# Pins.net
KiCad netlist of a schematic drawn in Altium Designer
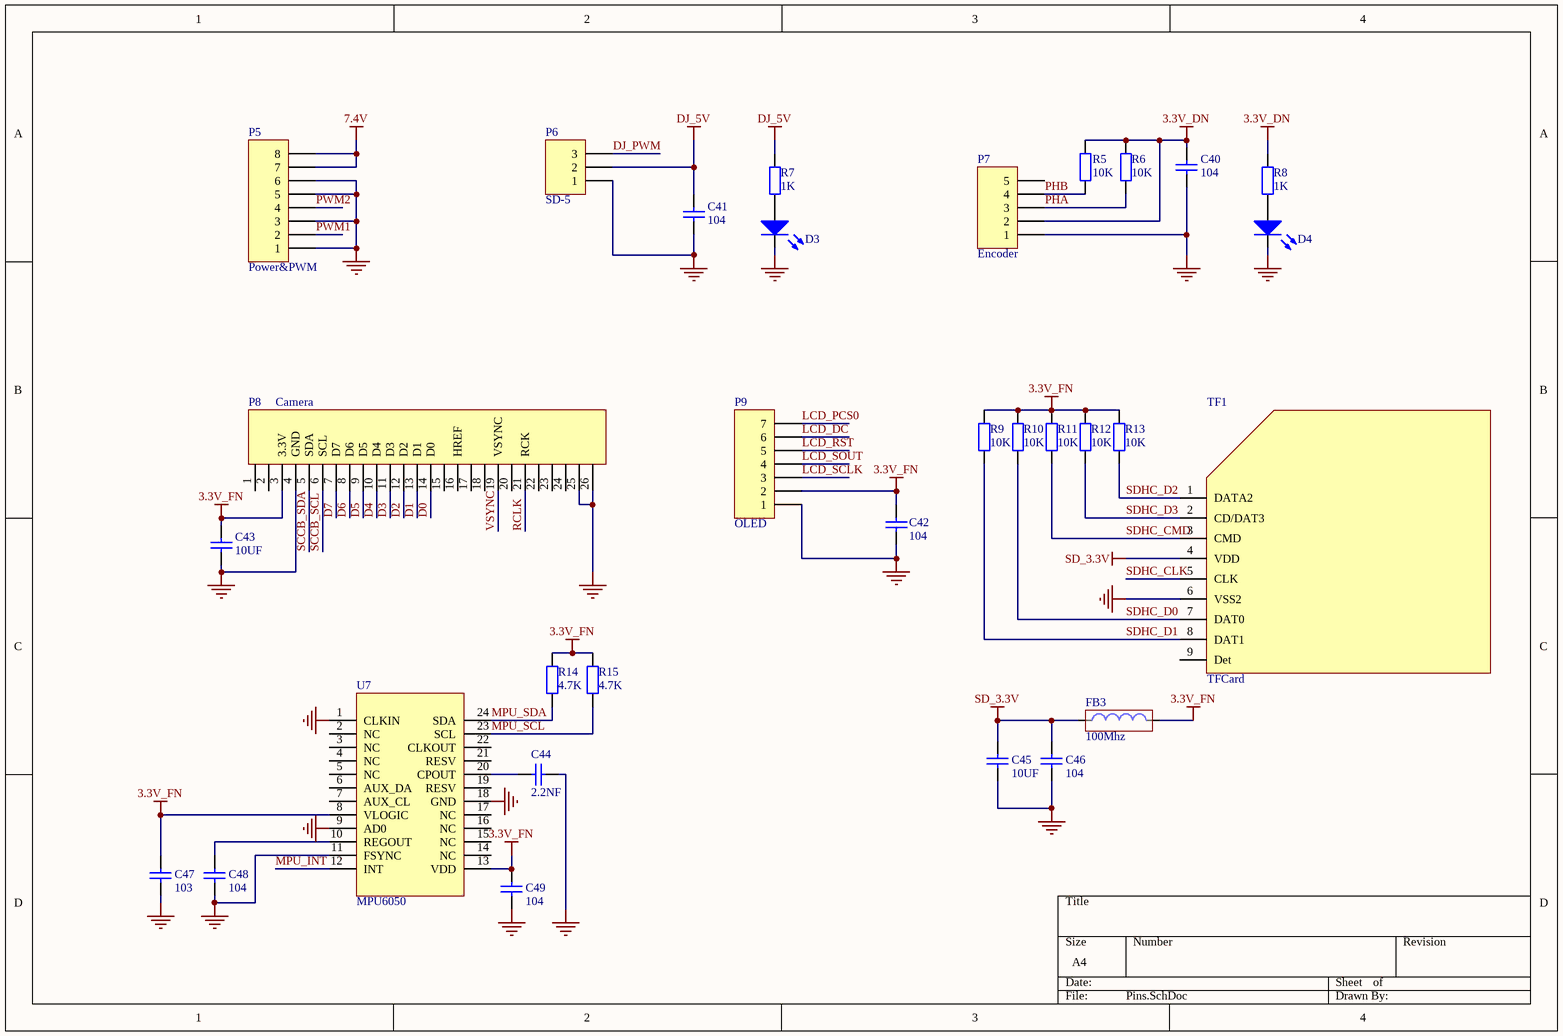
[diagram p0: Pins.SchDoc]

(export (version "E")
  (design (tool "Eeschema 10.0.6"))
  (components
    (comp (ref "C40") (value "104") (footprint "0805") (libsource (lib "飞思卡尔") (part "Cap")))
    (comp (ref "C41") (value "104") (footprint "0805") (libsource (lib "飞思卡尔") (part "Cap")))
    (comp (ref "C42") (value "104") (footprint "0805") (libsource (lib "飞思卡尔") (part "Cap")))
    (comp (ref "C43") (value "10UF") (footprint "1206") (libsource (lib "飞思卡尔") (part "Cap")))
    (comp (ref "C44") (value "2.2NF") (footprint "0805") (libsource (lib "飞思卡尔") (part "Cap")))
    (comp (ref "C45") (value "10UF") (footprint "1206") (libsource (lib "飞思卡尔") (part "Cap")))
    (comp (ref "C46") (value "104") (footprint "0805") (libsource (lib "飞思卡尔") (part "Cap")))
    (comp (ref "C47") (value "103") (footprint "0805") (libsource (lib "飞思卡尔") (part "Cap")))
    (comp (ref "C48") (value "104") (footprint "0805") (libsource (lib "飞思卡尔") (part "Cap")))
    (comp (ref "C49") (value "104") (footprint "0805") (libsource (lib "飞思卡尔") (part "Cap")))
    (comp (ref "D3") (value "Led") (footprint "0805") (libsource (lib "飞思卡尔") (part "Led")))
    (comp (ref "D4") (value "Led") (footprint "0805") (libsource (lib "飞思卡尔") (part "Led")))
    (comp (ref "FB3") (value "100Mhz") (footprint "0805") (libsource (lib "飞思卡尔") (part "Inductor")))
    (comp (ref "P5")
      (value "Power&PWM")
      (footprint "8P-2.54")
      (description "Header, 8-Pin")
      (fields (field (name "PUBLISHER") "Altium Limited"))
      (libsource (lib "Miscellaneous Connectors") (part "Header 8"))
    )
    (comp (ref "P6")
      (value "SD-5")
      (footprint "3PIN-2.54mm")
      (description "Header, 3-Pin")
      (fields (field (name "PUBLISHER") "Altium Limited"))
      (libsource (lib "Miscellaneous Connectors") (part "Header 3"))
    )
    (comp (ref "P7")
      (value "Encoder")
      (footprint "5P-2.54")
      (description "Header, 5-Pin")
      (fields (field (name "PUBLISHER") "Altium Limited"))
      (libsource (lib "Miscellaneous Connectors") (part "Header 5"))
    )
    (comp (ref "P8") (value "Camera") (footprint "FPC-0.5-24P") (libsource (lib "飞思卡尔") (part "野火鹰眼 排线")))
    (comp (ref "P9")
      (value "OLED")
      (footprint "HDR1X7")
      (description "Header, 7-Pin")
      (fields (field (name "PUBLISHER") "Altium Limited"))
      (libsource (lib "Miscellaneous Connectors") (part "Header 7"))
    )
    (comp (ref "R5") (value "10K") (footprint "0805") (libsource (lib "飞思卡尔") (part "Rest")))
    (comp (ref "R6") (value "10K") (footprint "0805") (libsource (lib "飞思卡尔") (part "Rest")))
    (comp (ref "R7") (value "1K") (footprint "0805") (libsource (lib "") (part "Rest_1")))
    (comp (ref "R8") (value "1K") (footprint "0805") (libsource (lib "") (part "Rest_1")))
    (comp (ref "R9") (value "10K") (footprint "0805") (libsource (lib "飞思卡尔") (part "Rest")))
    (comp (ref "R10") (value "10K") (footprint "0805") (libsource (lib "飞思卡尔") (part "Rest")))
    (comp (ref "R11") (value "10K") (footprint "0805") (libsource (lib "飞思卡尔") (part "Rest")))
    (comp (ref "R12") (value "10K") (footprint "0805") (libsource (lib "飞思卡尔") (part "Rest")))
    (comp (ref "R13") (value "10K") (footprint "0805") (libsource (lib "飞思卡尔") (part "Rest")))
    (comp (ref "R14") (value "4.7K") (footprint "0805") (libsource (lib "飞思卡尔") (part "Rest")))
    (comp (ref "R15") (value "4.7K") (footprint "0805") (libsource (lib "飞思卡尔") (part "Rest")))
    (comp (ref "TF1") (value "TFCard") (footprint "SD") (libsource (lib "飞思卡尔") (part "SD卡")))
    (comp (ref "U7") (value "MPU6050") (footprint "QFN-24P") (libsource (lib "飞思卡尔") (part "MPU6050")))
  )
  (nets
    (net (code "1") (name "/D0") (class "Default")
      (node (ref "P8") (pin "14") (pinfunction "D0_14") (pintype "passive"))
    )
    (net (code "2") (name "/D1") (class "Default")
      (node (ref "P8") (pin "13") (pinfunction "D1_13") (pintype "passive"))
    )
    (net (code "3") (name "/D2") (class "Default")
      (node (ref "P8") (pin "12") (pinfunction "D2_12") (pintype "passive"))
    )
    (net (code "4") (name "/D3") (class "Default")
      (node (ref "P8") (pin "11") (pinfunction "D3_11") (pintype "passive"))
    )
    (net (code "5") (name "/D4") (class "Default")
      (node (ref "P8") (pin "10") (pinfunction "D4_10") (pintype "passive"))
    )
    (net (code "6") (name "/D5") (class "Default")
      (node (ref "P8") (pin "9") (pinfunction "D5_9") (pintype "passive"))
    )
    (net (code "7") (name "/D6") (class "Default")
      (node (ref "P8") (pin "8") (pinfunction "D6_8") (pintype "passive"))
    )
    (net (code "8") (name "/D7") (class "Default")
      (node (ref "P8") (pin "7") (pinfunction "D7_7") (pintype "passive"))
    )
    (net (code "9") (name "/DJ_PWM") (class "Default")
      (node (ref "P6") (pin "3") (pinfunction "3_3") (pintype "passive"))
    )
    (net (code "10") (name "/LCD_DC") (class "Default")
      (node (ref "P9") (pin "6") (pinfunction "6_6") (pintype "passive"))
    )
    (net (code "11") (name "/LCD_PCS0") (class "Default")
      (node (ref "P9") (pin "7") (pinfunction "7_7") (pintype "passive"))
    )
    (net (code "12") (name "/LCD_RST") (class "Default")
      (node (ref "P9") (pin "5") (pinfunction "5_5") (pintype "passive"))
    )
    (net (code "13") (name "/LCD_SCLK") (class "Default")
      (node (ref "P9") (pin "3") (pinfunction "3_3") (pintype "passive"))
    )
    (net (code "14") (name "/LCD_SOUT") (class "Default")
      (node (ref "P9") (pin "4") (pinfunction "4_4") (pintype "passive"))
    )
    (net (code "15") (name "/MPU_INT") (class "Default")
      (node (ref "U7") (pin "12") (pinfunction "INT_12") (pintype "passive"))
    )
    (net (code "16") (name "/MPU_SCL") (class "Default")
      (node (ref "R15") (pin "1") (pinfunction "1_1") (pintype "passive"))
      (node (ref "U7") (pin "23") (pinfunction "SCL_23") (pintype "passive"))
    )
    (net (code "17") (name "/MPU_SDA") (class "Default")
      (node (ref "R14") (pin "1") (pinfunction "1_1") (pintype "passive"))
      (node (ref "U7") (pin "24") (pinfunction "SDA_24") (pintype "passive"))
    )
    (net (code "18") (name "/PHA") (class "Default")
      (node (ref "P7") (pin "3") (pinfunction "3_3") (pintype "passive"))
      (node (ref "R6") (pin "1") (pinfunction "1_1") (pintype "passive"))
    )
    (net (code "19") (name "/PHB") (class "Default")
      (node (ref "P7") (pin "4") (pinfunction "4_4") (pintype "passive"))
      (node (ref "R5") (pin "1") (pinfunction "1_1") (pintype "passive"))
    )
    (net (code "20") (name "/PWM1") (class "Default")
      (node (ref "P5") (pin "2") (pinfunction "2_2") (pintype "passive"))
    )
    (net (code "21") (name "/PWM2") (class "Default")
      (node (ref "P5") (pin "4") (pinfunction "4_4") (pintype "passive"))
    )
    (net (code "22") (name "/RCLK") (class "Default")
      (node (ref "P8") (pin "21") (pinfunction "RCK_21") (pintype "passive"))
    )
    (net (code "23") (name "/SCCB_SCL") (class "Default")
      (node (ref "P8") (pin "6") (pinfunction "SCL_6") (pintype "passive"))
    )
    (net (code "24") (name "/SCCB_SDA") (class "Default")
      (node (ref "P8") (pin "5") (pinfunction "SDA_5") (pintype "passive"))
    )
    (net (code "25") (name "/SDHC_CLK") (class "Default")
      (node (ref "TF1") (pin "5") (pinfunction "CLK_5") (pintype "passive"))
    )
    (net (code "26") (name "/SDHC_CMD") (class "Default")
      (node (ref "R11") (pin "1") (pinfunction "1_1") (pintype "passive"))
      (node (ref "TF1") (pin "3") (pinfunction "CMD_3") (pintype "passive"))
    )
    (net (code "27") (name "/SDHC_D0") (class "Default")
      (node (ref "R10") (pin "1") (pinfunction "1_1") (pintype "passive"))
      (node (ref "TF1") (pin "7") (pinfunction "DAT0_7") (pintype "passive"))
    )
    (net (code "28") (name "/SDHC_D1") (class "Default")
      (node (ref "R9") (pin "1") (pinfunction "1_1") (pintype "passive"))
      (node (ref "TF1") (pin "8") (pinfunction "DAT1_8") (pintype "passive"))
    )
    (net (code "29") (name "/SDHC_D2") (class "Default")
      (node (ref "R13") (pin "1") (pinfunction "1_1") (pintype "passive"))
      (node (ref "TF1") (pin "1") (pinfunction "DATA2_1") (pintype "passive"))
    )
    (net (code "30") (name "/SDHC_D3") (class "Default")
      (node (ref "R12") (pin "1") (pinfunction "1_1") (pintype "passive"))
      (node (ref "TF1") (pin "2") (pinfunction "CD/DAT3_2") (pintype "passive"))
    )
    (net (code "31") (name "/VSYNC") (class "Default")
      (node (ref "P8") (pin "19") (pinfunction "VSYNC_19") (pintype "passive"))
    )
    (net (code "32") (name "3.3V_DN") (class "Default")
      (node (ref "C40") (pin "2") (pinfunction "2_2") (pintype "passive"))
      (node (ref "P7") (pin "2") (pinfunction "2_2") (pintype "passive"))
      (node (ref "R5") (pin "2") (pinfunction "2_2") (pintype "passive"))
      (node (ref "R6") (pin "2") (pinfunction "2_2") (pintype "passive"))
      (node (ref "R8") (pin "1") (pinfunction "1_1") (pintype "passive"))
    )
    (net (code "33") (name "3.3V_FN") (class "Default")
      (node (ref "C42") (pin "1") (pinfunction "1_1") (pintype "passive"))
      (node (ref "C43") (pin "2") (pinfunction "2_2") (pintype "passive"))
      (node (ref "C47") (pin "1") (pinfunction "1_1") (pintype "passive"))
      (node (ref "C49") (pin "2") (pinfunction "2_2") (pintype "passive"))
      (node (ref "FB3") (pin "2") (pinfunction "2_2") (pintype "passive"))
      (node (ref "P8") (pin "3") (pinfunction "3.3V_3") (pintype "passive"))
      (node (ref "P9") (pin "2") (pinfunction "2_2") (pintype "passive"))
      (node (ref "R10") (pin "2") (pinfunction "2_2") (pintype "passive"))
      (node (ref "R11") (pin "2") (pinfunction "2_2") (pintype "passive"))
      (node (ref "R12") (pin "2") (pinfunction "2_2") (pintype "passive"))
      (node (ref "R13") (pin "2") (pinfunction "2_2") (pintype "passive"))
      (node (ref "R14") (pin "2") (pinfunction "2_2") (pintype "passive"))
      (node (ref "R15") (pin "2") (pinfunction "2_2") (pintype "passive"))
      (node (ref "R9") (pin "2") (pinfunction "2_2") (pintype "passive"))
      (node (ref "U7") (pin "13") (pinfunction "VDD_13") (pintype "passive"))
      (node (ref "U7") (pin "8") (pinfunction "VLOGIC_8") (pintype "passive"))
    )
    (net (code "34") (name "7.4V") (class "Default")
      (node (ref "P5") (pin "7") (pinfunction "7_7") (pintype "passive"))
      (node (ref "P5") (pin "8") (pinfunction "8_8") (pintype "passive"))
    )
    (net (code "35") (name "DJ_5V") (class "Default")
      (node (ref "C41") (pin "2") (pinfunction "2_2") (pintype "passive"))
      (node (ref "P6") (pin "2") (pinfunction "2_2") (pintype "passive"))
      (node (ref "R7") (pin "1") (pinfunction "1_1") (pintype "passive"))
    )
    (net (code "36") (name "GND") (class "Default")
      (node (ref "C40") (pin "1") (pinfunction "1_1") (pintype "passive"))
      (node (ref "C41") (pin "1") (pinfunction "1_1") (pintype "passive"))
      (node (ref "C42") (pin "2") (pinfunction "2_2") (pintype "passive"))
      (node (ref "C43") (pin "1") (pinfunction "1_1") (pintype "passive"))
      (node (ref "C44") (pin "2") (pinfunction "2_2") (pintype "passive"))
      (node (ref "C45") (pin "2") (pinfunction "2_2") (pintype "passive"))
      (node (ref "C46") (pin "1") (pinfunction "1_1") (pintype "passive"))
      (node (ref "C47") (pin "2") (pinfunction "2_2") (pintype "passive"))
      (node (ref "C48") (pin "1") (pinfunction "1_1") (pintype "passive"))
      (node (ref "C49") (pin "1") (pinfunction "1_1") (pintype "passive"))
      (node (ref "D3") (pin "2") (pinfunction "2_2") (pintype "passive"))
      (node (ref "D4") (pin "2") (pinfunction "2_2") (pintype "passive"))
      (node (ref "P5") (pin "1") (pinfunction "1_1") (pintype "passive"))
      (node (ref "P5") (pin "3") (pinfunction "3_3") (pintype "passive"))
      (node (ref "P5") (pin "5") (pinfunction "5_5") (pintype "passive"))
      (node (ref "P5") (pin "6") (pinfunction "6_6") (pintype "passive"))
      (node (ref "P6") (pin "1") (pinfunction "1_1") (pintype "passive"))
      (node (ref "P7") (pin "1") (pinfunction "1_1") (pintype "passive"))
      (node (ref "P8") (pin "25") (pinfunction "GND_25") (pintype "passive"))
      (node (ref "P8") (pin "26") (pinfunction "GND_26") (pintype "passive"))
      (node (ref "P8") (pin "4") (pinfunction "GND_4") (pintype "passive"))
      (node (ref "P9") (pin "1") (pinfunction "1_1") (pintype "passive"))
      (node (ref "TF1") (pin "6") (pinfunction "VSS2_6") (pintype "passive"))
      (node (ref "U7") (pin "1") (pinfunction "CLKIN_1") (pintype "passive"))
      (node (ref "U7") (pin "11") (pinfunction "FSYNC_11") (pintype "passive"))
      (node (ref "U7") (pin "18") (pinfunction "GND_18") (pintype "passive"))
      (node (ref "U7") (pin "9") (pinfunction "AD0_9") (pintype "passive"))
    )
    (net (code "37") (name "Net-(D3-Pad1)") (class "Default")
      (node (ref "D3") (pin "1") (pinfunction "1_1") (pintype "passive"))
      (node (ref "R7") (pin "2") (pinfunction "2_2") (pintype "passive"))
    )
    (net (code "38") (name "Net-(D4-Pad1)") (class "Default")
      (node (ref "D4") (pin "1") (pinfunction "1_1") (pintype "passive"))
      (node (ref "R8") (pin "2") (pinfunction "2_2") (pintype "passive"))
    )
    (net (code "39") (name "Net-(U7-CPOUT)") (class "Default")
      (node (ref "C44") (pin "1") (pinfunction "1_1") (pintype "passive"))
      (node (ref "U7") (pin "20") (pinfunction "CPOUT_20") (pintype "passive"))
    )
    (net (code "40") (name "Net-(U7-REGOUT)") (class "Default")
      (node (ref "C48") (pin "2") (pinfunction "2_2") (pintype "passive"))
      (node (ref "U7") (pin "10") (pinfunction "REGOUT_10") (pintype "passive"))
    )
    (net (code "41") (name "SD_3.3V") (class "Default")
      (node (ref "C45") (pin "1") (pinfunction "1_1") (pintype "passive"))
      (node (ref "C46") (pin "2") (pinfunction "2_2") (pintype "passive"))
      (node (ref "FB3") (pin "1") (pinfunction "1_1") (pintype "passive"))
      (node (ref "TF1") (pin "4") (pinfunction "VDD_4") (pintype "passive"))
    )
    (net (code "42") (name "unconnected-(P7-Pad5)") (class "Default")
      (node (ref "P7") (pin "5") (pinfunction "5_5") (pintype "passive"))
    )
    (net (code "43") (name "unconnected-(P8-0-Pad1)") (class "Default")
      (node (ref "P8") (pin "1") (pinfunction "0_1") (pintype "passive"))
    )
    (net (code "44") (name "unconnected-(P8-HREF-Pad16)") (class "Default")
      (node (ref "P8") (pin "16") (pinfunction "HREF_16") (pintype "passive"))
    )
    (net (code "45") (name "unconnected-(P8-OE-Pad15)") (class "Default")
      (node (ref "P8") (pin "15") (pinfunction "OE_15") (pintype "passive"))
    )
    (net (code "46") (name "unconnected-(P8-Pad2)") (class "Default")
      (node (ref "P8") (pin "2") (pinfunction "2_2") (pintype "passive"))
    )
    (net (code "47") (name "unconnected-(P8-Pad23)") (class "Default")
      (node (ref "P8") (pin "23") (pinfunction "23_23") (pintype "passive"))
    )
    (net (code "48") (name "unconnected-(P8-Pad24)") (class "Default")
      (node (ref "P8") (pin "24") (pinfunction "24_24") (pintype "passive"))
    )
    (net (code "49") (name "unconnected-(P8-REST-Pad22)") (class "Default")
      (node (ref "P8") (pin "22") (pinfunction "REST_22") (pintype "passive"))
    )
    (net (code "50") (name "unconnected-(P8-WEN-Pad17)") (class "Default")
      (node (ref "P8") (pin "17") (pinfunction "WEN_17") (pintype "passive"))
    )
    (net (code "51") (name "unconnected-(P8-WRST-Pad18)") (class "Default")
      (node (ref "P8") (pin "18") (pinfunction "WRST_18") (pintype "passive"))
    )
    (net (code "52") (name "unconnected-(P8-XCLK-Pad20)") (class "Default")
      (node (ref "P8") (pin "20") (pinfunction "XCLK_20") (pintype "passive"))
    )
    (net (code "53") (name "unconnected-(TF1-Det-Pad9)") (class "Default")
      (node (ref "TF1") (pin "9") (pinfunction "Det_9") (pintype "passive"))
    )
    (net (code "54") (name "unconnected-(U7-AUX_CL-Pad7)") (class "Default")
      (node (ref "U7") (pin "7") (pinfunction "AUX_CL_7") (pintype "passive"))
    )
    (net (code "55") (name "unconnected-(U7-AUX_DA-Pad6)") (class "Default")
      (node (ref "U7") (pin "6") (pinfunction "AUX_DA_6") (pintype "passive"))
    )
    (net (code "56") (name "unconnected-(U7-CLKOUT-Pad22)") (class "Default")
      (node (ref "U7") (pin "22") (pinfunction "CLKOUT_22") (pintype "passive"))
    )
    (net (code "57") (name "unconnected-(U7-NC-Pad2)") (class "Default")
      (node (ref "U7") (pin "2") (pinfunction "NC_2") (pintype "passive"))
    )
    (net (code "58") (name "unconnected-(U7-NC-Pad3)") (class "Default")
      (node (ref "U7") (pin "3") (pinfunction "NC_3") (pintype "passive"))
    )
    (net (code "59") (name "unconnected-(U7-NC-Pad4)") (class "Default")
      (node (ref "U7") (pin "4") (pinfunction "NC_4") (pintype "passive"))
    )
    (net (code "60") (name "unconnected-(U7-NC-Pad5)") (class "Default")
      (node (ref "U7") (pin "5") (pinfunction "NC_5") (pintype "passive"))
    )
    (net (code "61") (name "unconnected-(U7-NC-Pad14)") (class "Default")
      (node (ref "U7") (pin "14") (pinfunction "NC_14") (pintype "passive"))
    )
    (net (code "62") (name "unconnected-(U7-NC-Pad15)") (class "Default")
      (node (ref "U7") (pin "15") (pinfunction "NC_15") (pintype "passive"))
    )
    (net (code "63") (name "unconnected-(U7-NC-Pad16)") (class "Default")
      (node (ref "U7") (pin "16") (pinfunction "NC_16") (pintype "passive"))
    )
    (net (code "64") (name "unconnected-(U7-NC-Pad17)") (class "Default")
      (node (ref "U7") (pin "17") (pinfunction "NC_17") (pintype "passive"))
    )
    (net (code "65") (name "unconnected-(U7-RESV-Pad19)") (class "Default")
      (node (ref "U7") (pin "19") (pinfunction "RESV_19") (pintype "passive"))
    )
    (net (code "66") (name "unconnected-(U7-RESV-Pad21)") (class "Default")
      (node (ref "U7") (pin "21") (pinfunction "RESV_21") (pintype "passive"))
    )
  )
)
